# VCO_TOP.net
KiCad netlist of a schematic drawn in Altium Designer
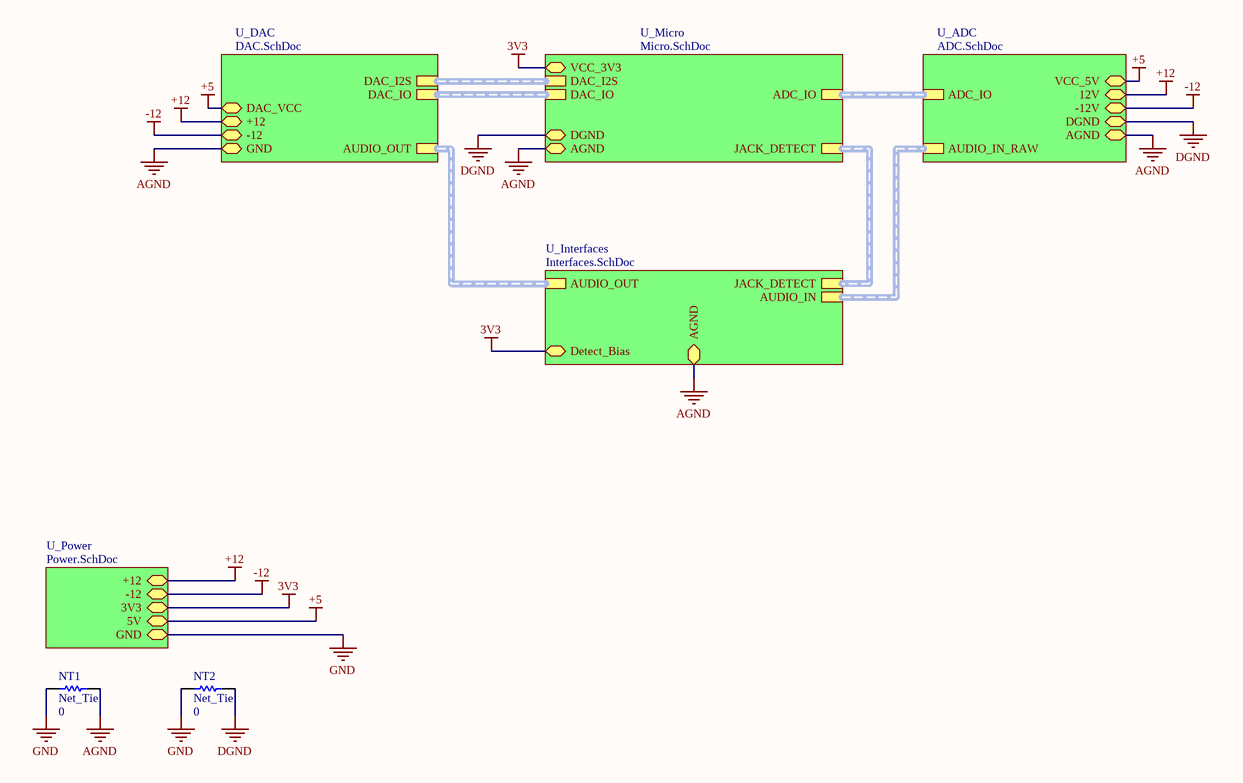
[diagram p0: VCO_TOP.SchDoc]

(export (version "E")
  (design (tool "Eeschema 10.0.6"))
  (components
    (comp (ref "NT1")
      (value "Net_Tie")
      (footprint "RES0603R")
      (description "Resistor")
      (fields (field (name "ALTIUM_VALUE") "0") (field (name "PUBLISHER") "Altium Limited"))
      (libsource (lib "Standard") (part "Res1"))
    )
    (comp (ref "NT2")
      (value "Net_Tie")
      (footprint "RES0603R")
      (description "Resistor")
      (fields (field (name "ALTIUM_VALUE") "0") (field (name "PUBLISHER") "Altium Limited"))
      (libsource (lib "Standard") (part "Res1"))
    )
  )
  (nets
    (net (code "11") (name "AGND") (class "Default")
      (node (ref "NT1") (pin "2") (pinfunction "2_2") (pintype "passive"))
    )
    (net (code "12") (name "DGND") (class "Default")
      (node (ref "NT2") (pin "2") (pinfunction "2_2") (pintype "passive"))
    )
    (net (code "13") (name "GND") (class "Default")
      (node (ref "NT1") (pin "1") (pinfunction "1_1") (pintype "passive"))
      (node (ref "NT2") (pin "1") (pinfunction "1_1") (pintype "passive"))
    )
  )
)
